# OTHER.net
KiCad netlist of a schematic drawn in Altium Designer
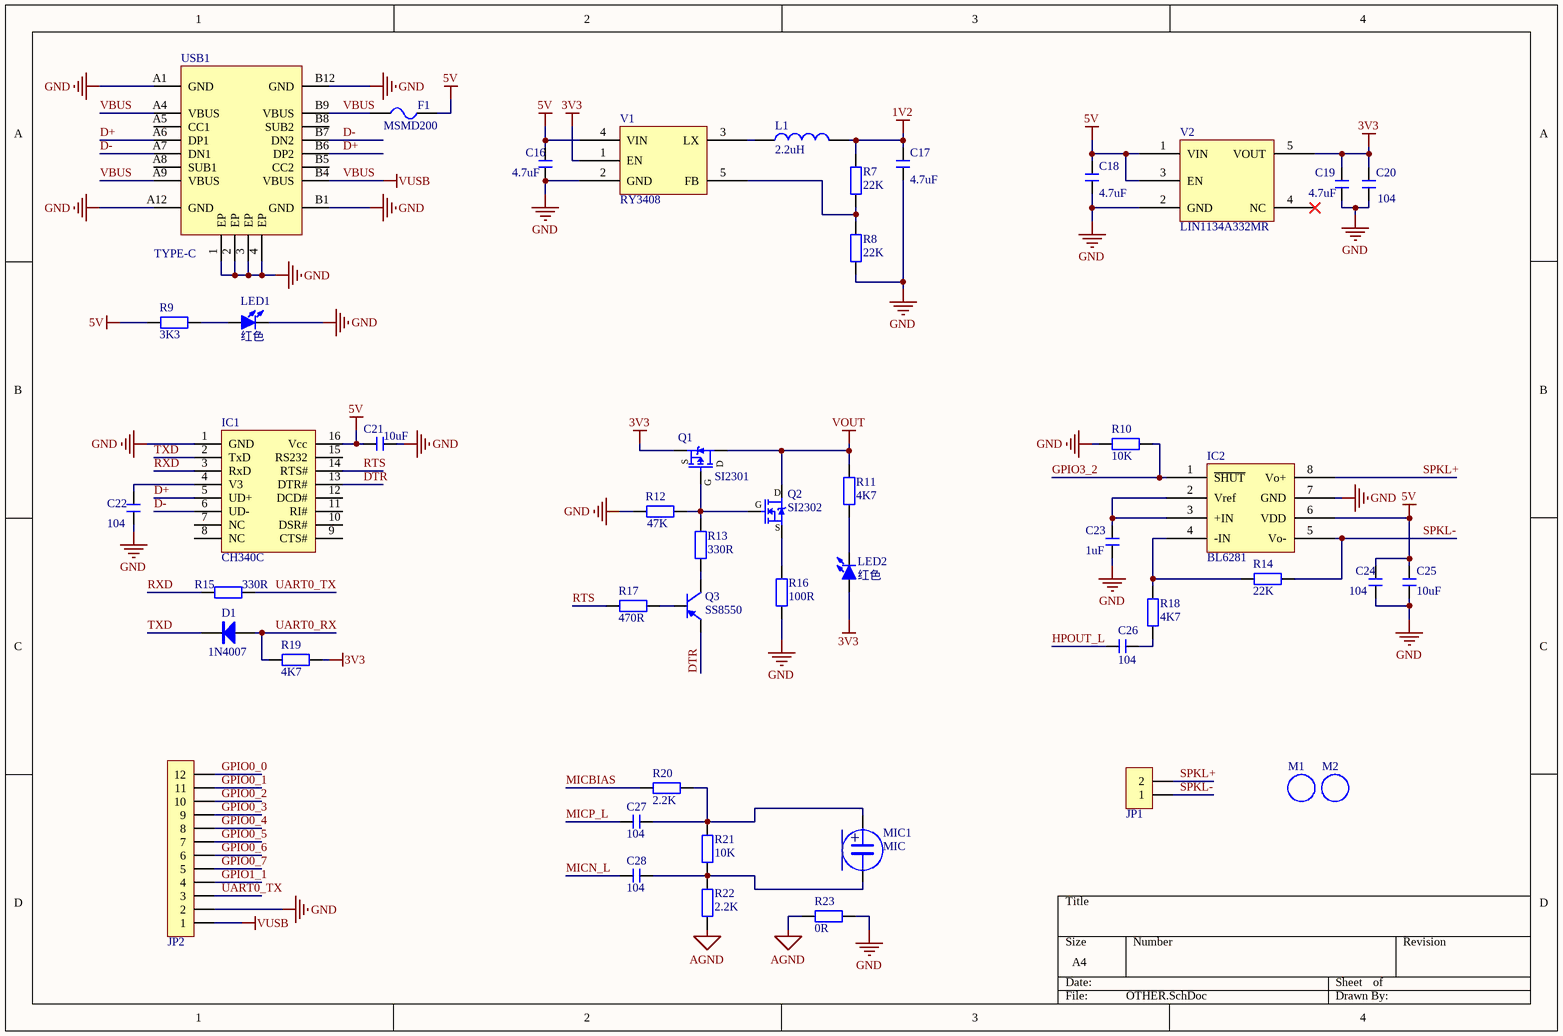
[diagram p0: OTHER.SchDoc]

(export (version "E")
  (design (tool "Eeschema 10.0.6"))
  (components
    (comp (ref "C16")
      (value "4.7uF")
      (footprint "C 0603_L")
      (description "无极性贴片电容")
      (fields (field (name "版权归属") "源创客"))
      (libsource (lib "3.1   - 电阻-电容-电感") (part "C"))
    )
    (comp (ref "C17")
      (value "4.7uF")
      (footprint "C 0603_L")
      (description "无极性贴片电容")
      (fields (field (name "版权归属") "源创客"))
      (libsource (lib "3.1   - 电阻-电容-电感") (part "C"))
    )
    (comp (ref "C18")
      (value "4.7uF")
      (footprint "C 0603_L")
      (description "无极性贴片电容")
      (fields (field (name "版权归属") "源创客"))
      (libsource (lib "3.1   - 电阻-电容-电感") (part "C"))
    )
    (comp (ref "C19")
      (value "4.7uF")
      (footprint "C 0603_L")
      (description "无极性贴片电容")
      (fields (field (name "版权归属") "源创客"))
      (libsource (lib "3.1   - 电阻-电容-电感") (part "C"))
    )
    (comp (ref "C20")
      (value "104")
      (footprint "C 0603_L")
      (description "无极性贴片电容")
      (fields (field (name "版权归属") "源创客"))
      (libsource (lib "3.1   - 电阻-电容-电感") (part "C"))
    )
    (comp (ref "C21")
      (value "10uF")
      (footprint "C 0805_L")
      (description "无极性贴片电容")
      (fields (field (name "版权归属") "源创客"))
      (libsource (lib "3.1   - 电阻-电容-电感") (part "C"))
    )
    (comp (ref "C22")
      (value "104")
      (footprint "C 0603_L")
      (description "无极性贴片电容")
      (fields (field (name "版权归属") "源创客"))
      (libsource (lib "3.1   - 电阻-电容-电感") (part "C"))
    )
    (comp (ref "C23")
      (value "1uF")
      (footprint "C 0603_L")
      (description "无极性贴片电容")
      (fields (field (name "版权归属") "源创客"))
      (libsource (lib "3.1   - 电阻-电容-电感") (part "C"))
    )
    (comp (ref "C24")
      (value "104")
      (footprint "C 0603_L")
      (description "无极性贴片电容")
      (fields (field (name "版权归属") "源创客"))
      (libsource (lib "3.1   - 电阻-电容-电感") (part "C"))
    )
    (comp (ref "C25")
      (value "10uF")
      (footprint "C 0603_L")
      (description "无极性贴片电容")
      (fields (field (name "版权归属") "源创客"))
      (libsource (lib "3.1   - 电阻-电容-电感") (part "C"))
    )
    (comp (ref "C26")
      (value "104")
      (footprint "C 0603_L")
      (description "无极性贴片电容")
      (fields (field (name "版权归属") "源创客"))
      (libsource (lib "3.1   - 电阻-电容-电感") (part "C"))
    )
    (comp (ref "C27")
      (value "104")
      (footprint "C 0603_L")
      (description "无极性贴片电容")
      (fields (field (name "版权归属") "源创客"))
      (libsource (lib "3.1   - 电阻-电容-电感") (part "C"))
    )
    (comp (ref "C28")
      (value "104")
      (footprint "C 0603_L")
      (description "无极性贴片电容")
      (fields (field (name "版权归属") "源创客"))
      (libsource (lib "3.1   - 电阻-电容-电感") (part "C"))
    )
    (comp (ref "D1")
      (value "1N4007")
      (footprint "SOD-123")
      (description "整流二极管")
      (fields (field (name "版权归属") "源创客"))
      (libsource (lib "8.1   - 二极管-整流桥") (part "1N4007"))
    )
    (comp (ref "F1")
      (value "MSMD200")
      (footprint "FU 0805")
      (description "贴片保险丝")
      (fields (field (name "版权归属") "源创客"))
      (libsource (lib "10.1 - 保险丝-晶振") (part "FU"))
    )
    (comp (ref "IC1")
      (value "CH340C")
      (footprint "SOP16_L")
      (description "串口转USB")
      (fields (field (name "版权归属") "源创客"))
      (libsource (lib "1.1   - IC芯片") (part "CH340G"))
    )
    (comp (ref "IC2")
      (value "BL6281")
      (footprint "SOP8_L")
      (description "音频功放")
      (libsource (lib "1.1   - IC芯片") (part "BL6281"))
    )
    (comp (ref "JP1")
      (value "HDR-1X2")
      (footprint "PH2.0-WS-2P")
      (description "2P接插件")
      (fields (field (name "版权归属") "源创客"))
      (libsource (lib "4.4   - 接插件-脚距2.0") (part "Header 2"))
    )
    (comp (ref "JP2")
      (value "HDR-1X12")
      (footprint "HDR2.54-LI-12P")
      (description "12P接插件")
      (fields (field (name "版权归属") "源创客"))
      (libsource (lib "4.5   - 接插件-脚距2.54") (part "Header 12"))
    )
    (comp (ref "L1")
      (value "2.2uH")
      (footprint "L 0805")
      (description "小功率贴片电感")
      (fields (field (name "版权归属") "源创客"))
      (libsource (lib "3.1   - 电阻-电容-电感") (part "L"))
    )
    (comp (ref "LED1")
      (value "红色")
      (footprint "LED 0603R")
      (description "贴片LED")
      (fields (field (name "版权归属") "源创客"))
      (libsource (lib "9.1   - LED") (part "LED-SMD"))
    )
    (comp (ref "LED2")
      (value "红色")
      (footprint "LED 0603R")
      (description "贴片LED")
      (fields (field (name "版权归属") "源创客"))
      (libsource (lib "9.1   - LED") (part "LED-SMD"))
    )
    (comp (ref "M1")
      (value "~")
      (footprint "M3 125X200")
      (description "铜柱孔")
      (fields (field (name "版权归属") "源创客"))
      (libsource (lib "15.1 - 未分类器件") (part "M3"))
    )
    (comp (ref "M2")
      (value "~")
      (footprint "M3 125X200")
      (description "铜柱孔")
      (fields (field (name "版权归属") "源创客"))
      (libsource (lib "15.1 - 未分类器件") (part "M3"))
    )
    (comp (ref "MIC1")
      (value "MIC")
      (footprint "MIC-6*2.7")
      (description "麦克风")
      (libsource (lib "11.1 - 传感元件") (part "MIC3"))
    )
    (comp (ref "Q1")
      (value "SI2301")
      (footprint "SOT23-3N")
      (description "P沟道 20V/2.8A")
      (fields (field (name "版权归属") "源创客"))
      (libsource (lib "6.1   - 场效应管-可控硅") (part "SI2301"))
    )
    (comp (ref "Q2")
      (value "SI2302")
      (footprint "SOT23-3N")
      (description "N沟道 20V/3A")
      (fields (field (name "版权归属") "源创客"))
      (libsource (lib "6.1   - 场效应管-可控硅") (part "SI2302"))
    )
    (comp (ref "Q3")
      (value "SS8550")
      (footprint "SOT23-3N")
      (description "高频放大-PNP型")
      (fields (field (name "版权归属") "源创客"))
      (libsource (lib "6.2   - 三极管") (part "8550-SMD"))
    )
    (comp (ref "R7")
      (value "22K")
      (footprint "R 0603_L")
      (description "贴片电阻")
      (fields (field (name "版权归属") "源创客"))
      (libsource (lib "3.1   - 电阻-电容-电感") (part "R"))
    )
    (comp (ref "R8")
      (value "22K")
      (footprint "R 0603_L")
      (description "贴片电阻")
      (fields (field (name "版权归属") "源创客"))
      (libsource (lib "3.1   - 电阻-电容-电感") (part "R"))
    )
    (comp (ref "R9")
      (value "3K3")
      (footprint "R 0603_L")
      (description "贴片电阻")
      (fields (field (name "版权归属") "源创客"))
      (libsource (lib "3.1   - 电阻-电容-电感") (part "R"))
    )
    (comp (ref "R10")
      (value "10K")
      (footprint "R 0603_L")
      (description "贴片电阻")
      (fields (field (name "版权归属") "源创客"))
      (libsource (lib "3.1   - 电阻-电容-电感") (part "R"))
    )
    (comp (ref "R11")
      (value "4K7")
      (footprint "R 0603_L")
      (description "贴片电阻")
      (fields (field (name "版权归属") "源创客"))
      (libsource (lib "3.1   - 电阻-电容-电感") (part "R"))
    )
    (comp (ref "R12")
      (value "47K")
      (footprint "R 0603_L")
      (description "贴片电阻")
      (fields (field (name "版权归属") "源创客"))
      (libsource (lib "3.1   - 电阻-电容-电感") (part "R"))
    )
    (comp (ref "R13")
      (value "330R")
      (footprint "R 0603_L")
      (description "贴片电阻")
      (fields (field (name "版权归属") "源创客"))
      (libsource (lib "3.1   - 电阻-电容-电感") (part "R"))
    )
    (comp (ref "R14")
      (value "22K")
      (footprint "R 0603_L")
      (description "贴片电阻")
      (fields (field (name "版权归属") "源创客"))
      (libsource (lib "3.1   - 电阻-电容-电感") (part "R"))
    )
    (comp (ref "R15")
      (value "330R")
      (footprint "R 0603_L")
      (description "贴片电阻")
      (fields (field (name "版权归属") "源创客"))
      (libsource (lib "3.1   - 电阻-电容-电感") (part "R"))
    )
    (comp (ref "R16")
      (value "100R")
      (footprint "R 0603_L")
      (description "贴片电阻")
      (fields (field (name "版权归属") "源创客"))
      (libsource (lib "3.1   - 电阻-电容-电感") (part "R"))
    )
    (comp (ref "R17")
      (value "470R")
      (footprint "R 0603_L")
      (description "贴片电阻")
      (fields (field (name "版权归属") "源创客"))
      (libsource (lib "3.1   - 电阻-电容-电感") (part "R"))
    )
    (comp (ref "R18")
      (value "4K7")
      (footprint "R 0603_L")
      (description "贴片电阻")
      (fields (field (name "版权归属") "源创客"))
      (libsource (lib "3.1   - 电阻-电容-电感") (part "R"))
    )
    (comp (ref "R19")
      (value "4K7")
      (footprint "R 0603_L")
      (description "贴片电阻")
      (fields (field (name "版权归属") "源创客"))
      (libsource (lib "3.1   - 电阻-电容-电感") (part "R"))
    )
    (comp (ref "R20")
      (value "2.2K")
      (footprint "R 0603_L")
      (description "贴片电阻")
      (fields (field (name "版权归属") "源创客"))
      (libsource (lib "3.1   - 电阻-电容-电感") (part "R"))
    )
    (comp (ref "R21")
      (value "10K")
      (footprint "R 0603_L")
      (description "贴片电阻")
      (fields (field (name "版权归属") "源创客"))
      (libsource (lib "3.1   - 电阻-电容-电感") (part "R"))
    )
    (comp (ref "R22")
      (value "2.2K")
      (footprint "R 0603_L")
      (description "贴片电阻")
      (fields (field (name "版权归属") "源创客"))
      (libsource (lib "3.1   - 电阻-电容-电感") (part "R"))
    )
    (comp (ref "R23")
      (value "0R")
      (footprint "R 0603_L")
      (description "贴片电阻")
      (fields (field (name "版权归属") "源创客"))
      (libsource (lib "3.1   - 电阻-电容-电感") (part "R"))
    )
    (comp (ref "USB1")
      (value "TYPE-C")
      (footprint "TYPE-C_16P")
      (description "16脚TYPE-C母座")
      (libsource (lib "4.1   - 接口类") (part "TYPE-C_16P"))
    )
    (comp (ref "V1")
      (value "RY3408")
      (footprint "SOT23-5N")
      (description "DC电源芯片")
      (libsource (lib "1.3   - 电源类芯片") (part "RY3408"))
    )
    (comp (ref "V2")
      (value "LIN1134A332MR")
      (footprint "SOT23-5L")
      (description "DC稳压芯片")
      (libsource (lib "1.3   - 电源类芯片") (part "LIN1134A332MR"))
    )
  )
  (nets
    (net (code "1") (name "/D+") (class "Default")
      (node (ref "IC1") (pin "5") (pinfunction "UD+_5") (pintype "passive"))
      (node (ref "USB1") (pin "A6") (pinfunction "DP1_A6") (pintype "passive"))
      (node (ref "USB1") (pin "B6") (pinfunction "DP2_B6") (pintype "passive"))
    )
    (net (code "2") (name "/D-") (class "Default")
      (node (ref "IC1") (pin "6") (pinfunction "UD-_6") (pintype "passive"))
      (node (ref "USB1") (pin "A7") (pinfunction "DN1_A7") (pintype "passive"))
      (node (ref "USB1") (pin "B7") (pinfunction "DN2_B7") (pintype "passive"))
    )
    (net (code "3") (name "/DTR") (class "Default")
      (node (ref "IC1") (pin "13") (pinfunction "DTR#_13") (pintype "passive"))
      (node (ref "Q3") (pin "2") (pinfunction "E_2") (pintype "passive"))
    )
    (net (code "4") (name "/GPIO0_0") (class "Default")
      (node (ref "JP2") (pin "12") (pinfunction "12_12") (pintype "passive"))
    )
    (net (code "5") (name "/GPIO0_1") (class "Default")
      (node (ref "JP2") (pin "11") (pinfunction "11_11") (pintype "passive"))
    )
    (net (code "6") (name "/GPIO0_2") (class "Default")
      (node (ref "JP2") (pin "10") (pinfunction "10_10") (pintype "passive"))
    )
    (net (code "7") (name "/GPIO0_3") (class "Default")
      (node (ref "JP2") (pin "9") (pinfunction "9_9") (pintype "passive"))
    )
    (net (code "8") (name "/GPIO0_4") (class "Default")
      (node (ref "JP2") (pin "8") (pinfunction "8_8") (pintype "passive"))
    )
    (net (code "9") (name "/GPIO0_5") (class "Default")
      (node (ref "JP2") (pin "7") (pinfunction "7_7") (pintype "passive"))
    )
    (net (code "10") (name "/GPIO0_6") (class "Default")
      (node (ref "JP2") (pin "6") (pinfunction "6_6") (pintype "passive"))
    )
    (net (code "11") (name "/GPIO0_7") (class "Default")
      (node (ref "JP2") (pin "5") (pinfunction "5_5") (pintype "passive"))
    )
    (net (code "12") (name "/GPIO1_1") (class "Default")
      (node (ref "JP2") (pin "4") (pinfunction "4_4") (pintype "passive"))
    )
    (net (code "13") (name "/GPIO3_2") (class "Default")
      (node (ref "IC2") (pin "1") (pinfunction "~{SHUT}_1") (pintype "passive"))
      (node (ref "R10") (pin "1") (pinfunction "1_1") (pintype "passive"))
    )
    (net (code "14") (name "/HPOUT_L") (class "Default")
      (node (ref "C26") (pin "2") (pinfunction "2_2") (pintype "passive"))
    )
    (net (code "15") (name "/MICBIAS") (class "Default")
      (node (ref "R20") (pin "1") (pinfunction "1_1") (pintype "passive"))
    )
    (net (code "16") (name "/MICN_L") (class "Default")
      (node (ref "C28") (pin "1") (pinfunction "1_1") (pintype "passive"))
    )
    (net (code "17") (name "/MICP_L") (class "Default")
      (node (ref "C27") (pin "1") (pinfunction "1_1") (pintype "passive"))
    )
    (net (code "18") (name "/RTS") (class "Default")
      (node (ref "IC1") (pin "14") (pinfunction "RTS#_14") (pintype "passive"))
      (node (ref "R17") (pin "2") (pinfunction "2_2") (pintype "passive"))
    )
    (net (code "19") (name "/RXD") (class "Default")
      (node (ref "IC1") (pin "3") (pinfunction "RxD_3") (pintype "passive"))
      (node (ref "R15") (pin "1") (pinfunction "1_1") (pintype "passive"))
    )
    (net (code "20") (name "/SPKL+") (class "Default")
      (node (ref "IC2") (pin "8") (pinfunction "Vo+_8") (pintype "passive"))
      (node (ref "JP1") (pin "2") (pinfunction "2_2") (pintype "passive"))
    )
    (net (code "21") (name "/SPKL-") (class "Default")
      (node (ref "IC2") (pin "5") (pinfunction "Vo-_5") (pintype "passive"))
      (node (ref "JP1") (pin "1") (pinfunction "1_1") (pintype "passive"))
      (node (ref "R14") (pin "1") (pinfunction "1_1") (pintype "passive"))
    )
    (net (code "22") (name "/TXD") (class "Default")
      (node (ref "D1") (pin "2") (pinfunction "K_2") (pintype "passive"))
      (node (ref "IC1") (pin "2") (pinfunction "TxD_2") (pintype "passive"))
    )
    (net (code "23") (name "/UART0_RX") (class "Default")
      (node (ref "D1") (pin "1") (pinfunction "A_1") (pintype "passive"))
      (node (ref "R19") (pin "2") (pinfunction "2_2") (pintype "passive"))
    )
    (net (code "24") (name "/UART0_TX") (class "Default")
      (node (ref "JP2") (pin "3") (pinfunction "3_3") (pintype "passive"))
      (node (ref "R15") (pin "2") (pinfunction "2_2") (pintype "passive"))
    )
    (net (code "25") (name "1V2") (class "Default")
      (node (ref "C17") (pin "2") (pinfunction "2_2") (pintype "passive"))
      (node (ref "L1") (pin "2") (pinfunction "2_2") (pintype "passive"))
      (node (ref "R7") (pin "2") (pinfunction "2_2") (pintype "passive"))
    )
    (net (code "26") (name "3V3") (class "Default")
      (node (ref "C19") (pin "2") (pinfunction "2_2") (pintype "passive"))
      (node (ref "C20") (pin "2") (pinfunction "2_2") (pintype "passive"))
      (node (ref "LED2") (pin "1") (pinfunction "A_1") (pintype "passive"))
      (node (ref "Q1") (pin "2") (pinfunction "S_2") (pintype "passive"))
      (node (ref "R19") (pin "1") (pinfunction "1_1") (pintype "passive"))
      (node (ref "V1") (pin "1") (pinfunction "EN_1") (pintype "passive"))
      (node (ref "V2") (pin "5") (pinfunction "VOUT_5") (pintype "passive"))
    )
    (net (code "27") (name "5V") (class "Default")
      (node (ref "C16") (pin "2") (pinfunction "2_2") (pintype "passive"))
      (node (ref "C18") (pin "2") (pinfunction "2_2") (pintype "passive"))
      (node (ref "C21") (pin "2") (pinfunction "2_2") (pintype "passive"))
      (node (ref "C24") (pin "1") (pinfunction "1_1") (pintype "passive"))
      (node (ref "C25") (pin "2") (pinfunction "2_2") (pintype "passive"))
      (node (ref "F1") (pin "2") (pinfunction "2_2") (pintype "passive"))
      (node (ref "IC1") (pin "16") (pinfunction "Vcc_16") (pintype "passive"))
      (node (ref "IC2") (pin "6") (pinfunction "VDD_6") (pintype "passive"))
      (node (ref "R9") (pin "1") (pinfunction "1_1") (pintype "passive"))
      (node (ref "V1") (pin "4") (pinfunction "VIN_4") (pintype "passive"))
      (node (ref "V2") (pin "1") (pinfunction "VIN_1") (pintype "passive"))
      (node (ref "V2") (pin "3") (pinfunction "EN_3") (pintype "passive"))
    )
    (net (code "28") (name "AGND") (class "Default")
      (node (ref "R22") (pin "2") (pinfunction "2_2") (pintype "passive"))
      (node (ref "R23") (pin "1") (pinfunction "1_1") (pintype "passive"))
    )
    (net (code "29") (name "GND") (class "Default")
      (node (ref "C16") (pin "1") (pinfunction "1_1") (pintype "passive"))
      (node (ref "C17") (pin "1") (pinfunction "1_1") (pintype "passive"))
      (node (ref "C18") (pin "1") (pinfunction "1_1") (pintype "passive"))
      (node (ref "C19") (pin "1") (pinfunction "1_1") (pintype "passive"))
      (node (ref "C20") (pin "1") (pinfunction "1_1") (pintype "passive"))
      (node (ref "C21") (pin "1") (pinfunction "1_1") (pintype "passive"))
      (node (ref "C22") (pin "1") (pinfunction "1_1") (pintype "passive"))
      (node (ref "C23") (pin "1") (pinfunction "1_1") (pintype "passive"))
      (node (ref "C24") (pin "2") (pinfunction "2_2") (pintype "passive"))
      (node (ref "C25") (pin "1") (pinfunction "1_1") (pintype "passive"))
      (node (ref "IC1") (pin "1") (pinfunction "GND_1") (pintype "passive"))
      (node (ref "IC2") (pin "7") (pinfunction "GND_7") (pintype "passive"))
      (node (ref "JP2") (pin "2") (pinfunction "2_2") (pintype "passive"))
      (node (ref "LED1") (pin "2") (pinfunction "K_2") (pintype "passive"))
      (node (ref "R10") (pin "2") (pinfunction "2_2") (pintype "passive"))
      (node (ref "R12") (pin "2") (pinfunction "2_2") (pintype "passive"))
      (node (ref "R16") (pin "2") (pinfunction "2_2") (pintype "passive"))
      (node (ref "R23") (pin "2") (pinfunction "2_2") (pintype "passive"))
      (node (ref "R8") (pin "1") (pinfunction "1_1") (pintype "passive"))
      (node (ref "USB1") (pin "1") (pinfunction "EP_1") (pintype "passive"))
      (node (ref "USB1") (pin "2") (pinfunction "EP_2") (pintype "passive"))
      (node (ref "USB1") (pin "3") (pinfunction "EP_3") (pintype "passive"))
      (node (ref "USB1") (pin "4") (pinfunction "EP_4") (pintype "passive"))
      (node (ref "USB1") (pin "A1") (pinfunction "GND_A1") (pintype "passive"))
      (node (ref "USB1") (pin "A12") (pinfunction "GND_A12") (pintype "passive"))
      (node (ref "USB1") (pin "B1") (pinfunction "GND_B1") (pintype "passive"))
      (node (ref "USB1") (pin "B12") (pinfunction "GND_B12") (pintype "passive"))
      (node (ref "V1") (pin "2") (pinfunction "GND_2") (pintype "passive"))
      (node (ref "V2") (pin "2") (pinfunction "GND_2") (pintype "passive"))
    )
    (net (code "30") (name "Net-(C26-Pad1)") (class "Default")
      (node (ref "C26") (pin "1") (pinfunction "1_1") (pintype "passive"))
      (node (ref "R18") (pin "2") (pinfunction "2_2") (pintype "passive"))
    )
    (net (code "31") (name "Net-(C27-Pad2)") (class "Default")
      (node (ref "C27") (pin "2") (pinfunction "2_2") (pintype "passive"))
      (node (ref "MIC1") (pin "1") (pinfunction "1_1") (pintype "passive"))
      (node (ref "R20") (pin "2") (pinfunction "2_2") (pintype "passive"))
      (node (ref "R21") (pin "1") (pinfunction "1_1") (pintype "passive"))
    )
    (net (code "32") (name "Net-(C28-Pad2)") (class "Default")
      (node (ref "C28") (pin "2") (pinfunction "2_2") (pintype "passive"))
      (node (ref "MIC1") (pin "2") (pinfunction "2_2") (pintype "passive"))
      (node (ref "R21") (pin "2") (pinfunction "2_2") (pintype "passive"))
      (node (ref "R22") (pin "1") (pinfunction "1_1") (pintype "passive"))
    )
    (net (code "33") (name "Net-(IC1-V3)") (class "Default")
      (node (ref "C22") (pin "2") (pinfunction "2_2") (pintype "passive"))
      (node (ref "IC1") (pin "4") (pinfunction "V3_4") (pintype "passive"))
    )
    (net (code "34") (name "Net-(IC2-+IN)") (class "Default")
      (node (ref "C23") (pin "2") (pinfunction "2_2") (pintype "passive"))
      (node (ref "IC2") (pin "2") (pinfunction "Vref_2") (pintype "passive"))
      (node (ref "IC2") (pin "3") (pinfunction "+IN_3") (pintype "passive"))
    )
    (net (code "35") (name "Net-(IC2--IN)") (class "Default")
      (node (ref "IC2") (pin "4") (pinfunction "-IN_4") (pintype "passive"))
      (node (ref "R14") (pin "2") (pinfunction "2_2") (pintype "passive"))
      (node (ref "R18") (pin "1") (pinfunction "1_1") (pintype "passive"))
    )
    (net (code "36") (name "Net-(LED1-A)") (class "Default")
      (node (ref "LED1") (pin "1") (pinfunction "A_1") (pintype "passive"))
      (node (ref "R9") (pin "2") (pinfunction "2_2") (pintype "passive"))
    )
    (net (code "37") (name "Net-(LED2-K)") (class "Default")
      (node (ref "LED2") (pin "2") (pinfunction "K_2") (pintype "passive"))
      (node (ref "R11") (pin "1") (pinfunction "1_1") (pintype "passive"))
    )
    (net (code "38") (name "Net-(Q1-G)") (class "Default")
      (node (ref "Q1") (pin "1") (pinfunction "G_1") (pintype "passive"))
      (node (ref "Q2") (pin "1") (pinfunction "G_1") (pintype "passive"))
      (node (ref "R12") (pin "1") (pinfunction "1_1") (pintype "passive"))
      (node (ref "R13") (pin "2") (pinfunction "2_2") (pintype "passive"))
    )
    (net (code "39") (name "Net-(Q2-S)") (class "Default")
      (node (ref "Q2") (pin "2") (pinfunction "S_2") (pintype "passive"))
      (node (ref "R16") (pin "1") (pinfunction "1_1") (pintype "passive"))
    )
    (net (code "40") (name "Net-(Q3-B)") (class "Default")
      (node (ref "Q3") (pin "1") (pinfunction "B_1") (pintype "passive"))
      (node (ref "R17") (pin "1") (pinfunction "1_1") (pintype "passive"))
    )
    (net (code "41") (name "Net-(Q3-C)") (class "Default")
      (node (ref "Q3") (pin "3") (pinfunction "C_3") (pintype "passive"))
      (node (ref "R13") (pin "1") (pinfunction "1_1") (pintype "passive"))
    )
    (net (code "42") (name "Net-(V1-FB)") (class "Default")
      (node (ref "R7") (pin "1") (pinfunction "1_1") (pintype "passive"))
      (node (ref "R8") (pin "2") (pinfunction "2_2") (pintype "passive"))
      (node (ref "V1") (pin "5") (pinfunction "FB_5") (pintype "passive"))
    )
    (net (code "43") (name "Net-(V1-LX)") (class "Default")
      (node (ref "L1") (pin "1") (pinfunction "1_1") (pintype "passive"))
      (node (ref "V1") (pin "3") (pinfunction "LX_3") (pintype "passive"))
    )
    (net (code "44") (name "VOUT") (class "Default")
      (node (ref "Q1") (pin "3") (pinfunction "D_3") (pintype "passive"))
      (node (ref "Q2") (pin "3") (pinfunction "D_3") (pintype "passive"))
      (node (ref "R11") (pin "2") (pinfunction "2_2") (pintype "passive"))
    )
    (net (code "45") (name "VUSB") (class "Default")
      (node (ref "F1") (pin "1") (pinfunction "1_1") (pintype "passive"))
      (node (ref "JP2") (pin "1") (pinfunction "1_1") (pintype "passive"))
      (node (ref "USB1") (pin "A4") (pinfunction "VBUS_A4") (pintype "passive"))
      (node (ref "USB1") (pin "A9") (pinfunction "VBUS_A9") (pintype "passive"))
      (node (ref "USB1") (pin "B4") (pinfunction "VBUS_B4") (pintype "passive"))
      (node (ref "USB1") (pin "B9") (pinfunction "VBUS_B9") (pintype "passive"))
    )
    (net (code "46") (name "unconnected-(IC1-CTS#-Pad9)") (class "Default")
      (node (ref "IC1") (pin "9") (pinfunction "CTS#_9") (pintype "passive"))
    )
    (net (code "47") (name "unconnected-(IC1-DCD#-Pad12)") (class "Default")
      (node (ref "IC1") (pin "12") (pinfunction "DCD#_12") (pintype "passive"))
    )
    (net (code "48") (name "unconnected-(IC1-DSR#-Pad10)") (class "Default")
      (node (ref "IC1") (pin "10") (pinfunction "DSR#_10") (pintype "passive"))
    )
    (net (code "49") (name "unconnected-(IC1-NC-Pad7)") (class "Default")
      (node (ref "IC1") (pin "7") (pinfunction "NC_7") (pintype "passive"))
    )
    (net (code "50") (name "unconnected-(IC1-NC-Pad8)") (class "Default")
      (node (ref "IC1") (pin "8") (pinfunction "NC_8") (pintype "passive"))
    )
    (net (code "51") (name "unconnected-(IC1-RI#-Pad11)") (class "Default")
      (node (ref "IC1") (pin "11") (pinfunction "RI#_11") (pintype "passive"))
    )
    (net (code "52") (name "unconnected-(IC1-RS232-Pad15)") (class "Default")
      (node (ref "IC1") (pin "15") (pinfunction "RS232_15") (pintype "passive"))
    )
    (net (code "53") (name "unconnected-(USB1-CC1-PadA5)") (class "Default")
      (node (ref "USB1") (pin "A5") (pinfunction "CC1_A5") (pintype "passive"))
    )
    (net (code "54") (name "unconnected-(USB1-CC2-PadB5)") (class "Default")
      (node (ref "USB1") (pin "B5") (pinfunction "CC2_B5") (pintype "passive"))
    )
    (net (code "55") (name "unconnected-(USB1-SUB1-PadA8)") (class "Default")
      (node (ref "USB1") (pin "A8") (pinfunction "SUB1_A8") (pintype "passive"))
    )
    (net (code "56") (name "unconnected-(USB1-SUB2-PadB8)") (class "Default")
      (node (ref "USB1") (pin "B8") (pinfunction "SUB2_B8") (pintype "passive"))
    )
    (net (code "57") (name "unconnected-(V2-NC-Pad4)") (class "Default")
      (node (ref "V2") (pin "4") (pinfunction "NC_4") (pintype "passive+no_connect"))
    )
  )
)
